# sch.net
KiCad netlist of a schematic drawn in Altium Designer
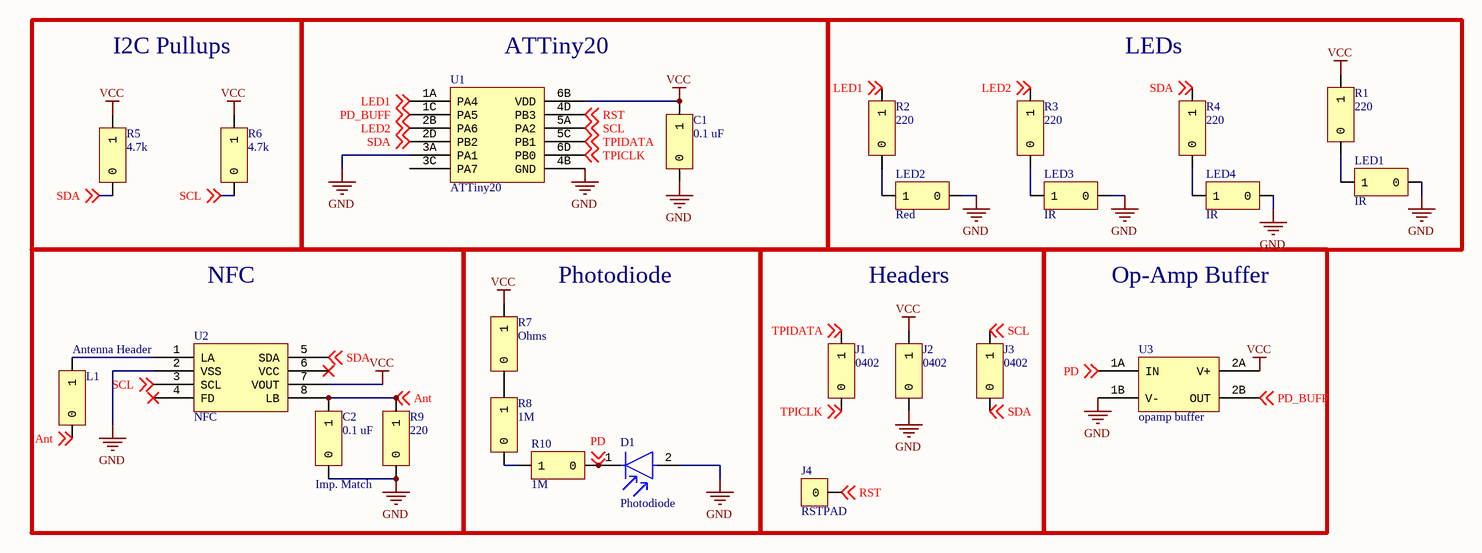
[diagram p0: sch.SchDoc]

(export (version "E")
  (design (tool "Eeschema 10.0.6"))
  (components
    (comp (ref "C1")
      (value "0.1 uF")
      (footprint "01005")
      (description "01005 Component")
      (fields (field (name "MPN") "CL02A104KQ2NNNC"))
      (libsource (lib "schlib") (part "01005"))
    )
    (comp (ref "C2")
      (value "0.1 uF")
      (footprint "01005")
      (description "01005 Component")
      (fields (field (name "MPN") "CL02A104KQ2NNNC"))
      (libsource (lib "schlib") (part "01005"))
    )
    (comp (ref "D1")
      (value "Photodiode")
      (footprint "FP-6_541-5064_01-4-MFG")
      (description "0805 PHOTODIODE\r\ntemd7000x01")
      (fields
        (field (name "MANUFACTURER") "Vishay")
        (field (name "OCTOPART") "https://octopart.com/temd6200fx01-vishay-19158932")
      )
      (libsource (lib "Altium Content Vault") (part "9b7c99953c265a88c20b8f1023d9605"))
    )
    (comp (ref "J1")
      (value "0402")
      (footprint "0402")
      (description "0402 Component")
      (libsource (lib "schlib") (part "0402"))
    )
    (comp (ref "J2")
      (value "0402")
      (footprint "0402")
      (description "0402 Component")
      (libsource (lib "schlib") (part "0402"))
    )
    (comp (ref "J3")
      (value "0402")
      (footprint "0402")
      (description "0402 Component")
      (libsource (lib "schlib") (part "0402"))
    )
    (comp (ref "J4") (value "RSTPAD") (footprint "RSTPAD") (libsource (lib "schlib") (part "RSTPAD")))
    (comp (ref "L1")
      (value "Antenna Header")
      (footprint "0402")
      (description "0402 Component")
      (libsource (lib "schlib") (part "0402"))
    )
    (comp (ref "LED1")
      (value "IR")
      (footprint "0402")
      (description "0402 Component\r\nSFH 4043")
      (fields (field (name "MPN") "SFH 4043"))
      (libsource (lib "") (part "0402_1"))
    )
    (comp (ref "LED2")
      (value "Red")
      (footprint "0201")
      (description "0201 Component\r\nXZMDR155W")
      (fields (field (name "MPN") "XZMDR155W"))
      (libsource (lib "schlib") (part "0201"))
    )
    (comp (ref "LED3")
      (value "IR")
      (footprint "0402")
      (description "0402 Component\r\nSFH 4043")
      (fields (field (name "MPN") "SFH 4043"))
      (libsource (lib "") (part "0402_1"))
    )
    (comp (ref "LED4")
      (value "IR")
      (footprint "0402")
      (description "0402 Component\r\nSFH 4043")
      (fields (field (name "MPN") "SFH 4043"))
      (libsource (lib "") (part "0402_1"))
    )
    (comp (ref "R1")
      (value "220")
      (footprint "01005")
      (description "01005 Component\r\nCRCW0100220RFREL")
      (fields (field (name "MPN") "CRCW0100220RFREL"))
      (libsource (lib "schlib") (part "01005"))
    )
    (comp (ref "R2")
      (value "220")
      (footprint "01005")
      (description "01005 Component\r\nCRCW0100220RFREL")
      (fields (field (name "MPN") "CRCW0100220RFREL"))
      (libsource (lib "schlib") (part "01005"))
    )
    (comp (ref "R3")
      (value "220")
      (footprint "01005")
      (description "01005 Component\r\nCRCW0100220RFREL")
      (fields (field (name "MPN") "CRCW0100220RFREL"))
      (libsource (lib "schlib") (part "01005"))
    )
    (comp (ref "R4")
      (value "220")
      (footprint "01005")
      (description "01005 Component\r\nCRCW0100220RFREL")
      (fields (field (name "MPN") "CRCW0100220RFREL"))
      (libsource (lib "schlib") (part "01005"))
    )
    (comp (ref "R5")
      (value "4.7k")
      (footprint "01005")
      (description "01005 Component")
      (fields (field (name "MPN") "CL02A104KQ2NNNC"))
      (libsource (lib "schlib") (part "01005"))
    )
    (comp (ref "R6")
      (value "4.7k")
      (footprint "01005")
      (description "01005 Component")
      (fields (field (name "MPN") "CL02A104KQ2NNNC"))
      (libsource (lib "schlib") (part "01005"))
    )
    (comp (ref "R7")
      (value "Ohms")
      (footprint "01005")
      (description "01005 Component\r\nCRCW01001M00FREL\r\n<Placeholder if more gain is necessary>")
      (fields (field (name "MPN") "CRCW01001M00FREL"))
      (libsource (lib "schlib") (part "01005"))
    )
    (comp (ref "R8")
      (value "1M")
      (footprint "01005")
      (description "01005 Component\r\nCRCW01001M00FREL")
      (fields (field (name "MPN") "CRCW01001M00FREL"))
      (libsource (lib "schlib") (part "01005"))
    )
    (comp (ref "R9")
      (value "220")
      (footprint "01005")
      (description "01005 Component\r\nCRCW0100220RFREL")
      (fields (field (name "MPN") "CRCW0100220RFREL"))
      (libsource (lib "schlib") (part "01005"))
    )
    (comp (ref "R10")
      (value "1M")
      (footprint "01005")
      (description "01005 Component\r\nCRCW01001M00FREL")
      (fields (field (name "MPN") "CRCW01001M00FREL"))
      (libsource (lib "") (part "01005_1"))
    )
    (comp (ref "U1")
      (value "ATTiny20")
      (footprint "Large_attiny")
      (libsource (lib "schlib") (part "ATTiny20"))
    )
    (comp (ref "U2") (value "NFC") (footprint "NFC") (libsource (lib "schlib") (part "NFC")))
    (comp (ref "U3") (value "opamp buffer") (footprint "opamp") (libsource (lib "schlib") (part "Op-amp")))
  )
  (nets
    (net (code "1") (name "Ant") (class "Default")
      (node (ref "C2") (pin "1") (pinfunction "1_1") (pintype "passive"))
      (node (ref "L1") (pin "0") (pinfunction "0_0") (pintype "passive"))
      (node (ref "R9") (pin "1") (pinfunction "1_1") (pintype "passive"))
      (node (ref "U2") (pin "8") (pinfunction "LB_8") (pintype "passive"))
    )
    (net (code "2") (name "GND") (class "Default")
      (node (ref "C1") (pin "0") (pinfunction "0_0") (pintype "passive"))
      (node (ref "C2") (pin "0") (pinfunction "0_0") (pintype "passive"))
      (node (ref "D1") (pin "2") (pinfunction "A_2") (pintype "passive"))
      (node (ref "J2") (pin "0") (pinfunction "0_0") (pintype "passive"))
      (node (ref "LED1") (pin "0") (pinfunction "0_0") (pintype "passive"))
      (node (ref "LED2") (pin "0") (pinfunction "0_0") (pintype "passive"))
      (node (ref "LED3") (pin "0") (pinfunction "0_0") (pintype "passive"))
      (node (ref "LED4") (pin "0") (pinfunction "0_0") (pintype "passive"))
      (node (ref "R9") (pin "0") (pinfunction "0_0") (pintype "passive"))
      (node (ref "U1") (pin "3A") (pinfunction "PA1_3A") (pintype "passive"))
      (node (ref "U1") (pin "4B") (pinfunction "GND_4B") (pintype "passive"))
      (node (ref "U2") (pin "2") (pinfunction "VSS_2") (pintype "passive"))
      (node (ref "U3") (pin "1B") (pinfunction "V-_1B") (pintype "passive"))
    )
    (net (code "3") (name "LED1") (class "Default")
      (node (ref "R2") (pin "1") (pinfunction "1_1") (pintype "passive"))
      (node (ref "U1") (pin "1A") (pinfunction "PA4_1A") (pintype "passive"))
    )
    (net (code "4") (name "LED2") (class "Default")
      (node (ref "R3") (pin "1") (pinfunction "1_1") (pintype "passive"))
      (node (ref "U1") (pin "2B") (pinfunction "PA6_2B") (pintype "passive"))
    )
    (net (code "5") (name "Net-(LED1-Pad1)") (class "Default")
      (node (ref "LED1") (pin "1") (pinfunction "1_1") (pintype "passive"))
      (node (ref "R1") (pin "0") (pinfunction "0_0") (pintype "passive"))
    )
    (net (code "6") (name "Net-(LED2-Pad1)") (class "Default")
      (node (ref "LED2") (pin "1") (pinfunction "1_1") (pintype "passive"))
      (node (ref "R2") (pin "0") (pinfunction "0_0") (pintype "passive"))
    )
    (net (code "7") (name "Net-(LED3-Pad1)") (class "Default")
      (node (ref "LED3") (pin "1") (pinfunction "1_1") (pintype "passive"))
      (node (ref "R3") (pin "0") (pinfunction "0_0") (pintype "passive"))
    )
    (net (code "8") (name "Net-(LED4-Pad1)") (class "Default")
      (node (ref "LED4") (pin "1") (pinfunction "1_1") (pintype "passive"))
      (node (ref "R4") (pin "0") (pinfunction "0_0") (pintype "passive"))
    )
    (net (code "9") (name "Net-(R7-Pad0)") (class "Default")
      (node (ref "R7") (pin "0") (pinfunction "0_0") (pintype "passive"))
      (node (ref "R8") (pin "1") (pinfunction "1_1") (pintype "passive"))
    )
    (net (code "10") (name "Net-(R10-Pad1)") (class "Default")
      (node (ref "R10") (pin "1") (pinfunction "1_1") (pintype "passive"))
      (node (ref "R8") (pin "0") (pinfunction "0_0") (pintype "passive"))
    )
    (net (code "11") (name "Net-(U2-LA)") (class "Default")
      (node (ref "L1") (pin "1") (pinfunction "1_1") (pintype "passive"))
      (node (ref "U2") (pin "1") (pinfunction "LA_1") (pintype "passive"))
    )
    (net (code "12") (name "PD") (class "Default")
      (node (ref "D1") (pin "1") (pinfunction "C_1") (pintype "passive"))
      (node (ref "R10") (pin "0") (pinfunction "0_0") (pintype "passive"))
      (node (ref "U3") (pin "1A") (pinfunction "IN_1A") (pintype "passive"))
    )
    (net (code "13") (name "PD_BUFF") (class "Default")
      (node (ref "U1") (pin "1C") (pinfunction "PA5_1C") (pintype "passive"))
      (node (ref "U3") (pin "2B") (pinfunction "OUT_2B") (pintype "passive"))
    )
    (net (code "14") (name "RST") (class "Default")
      (node (ref "J4") (pin "0") (pinfunction "0_0") (pintype "passive"))
      (node (ref "U1") (pin "4D") (pinfunction "PB3_4D") (pintype "passive"))
    )
    (net (code "15") (name "SCL") (class "Default")
      (node (ref "J3") (pin "1") (pinfunction "1_1") (pintype "passive"))
      (node (ref "R6") (pin "0") (pinfunction "0_0") (pintype "passive"))
      (node (ref "U1") (pin "5A") (pinfunction "PA2_5A") (pintype "passive"))
      (node (ref "U2") (pin "3") (pinfunction "SCL_3") (pintype "passive"))
    )
    (net (code "16") (name "SDA") (class "Default")
      (node (ref "J3") (pin "0") (pinfunction "0_0") (pintype "passive"))
      (node (ref "R4") (pin "1") (pinfunction "1_1") (pintype "passive"))
      (node (ref "R5") (pin "0") (pinfunction "0_0") (pintype "passive"))
      (node (ref "U1") (pin "2D") (pinfunction "PB2_2D") (pintype "passive"))
      (node (ref "U2") (pin "5") (pinfunction "SDA_5") (pintype "passive"))
    )
    (net (code "17") (name "TPICLK") (class "Default")
      (node (ref "J1") (pin "0") (pinfunction "0_0") (pintype "passive"))
      (node (ref "U1") (pin "6D") (pinfunction "PB0_6D") (pintype "passive"))
    )
    (net (code "18") (name "TPIDATA") (class "Default")
      (node (ref "J1") (pin "1") (pinfunction "1_1") (pintype "passive"))
      (node (ref "U1") (pin "5C") (pinfunction "PB1_5C") (pintype "passive"))
    )
    (net (code "19") (name "VCC") (class "Default")
      (node (ref "C1") (pin "1") (pinfunction "1_1") (pintype "passive"))
      (node (ref "J2") (pin "1") (pinfunction "1_1") (pintype "passive"))
      (node (ref "R1") (pin "1") (pinfunction "1_1") (pintype "passive"))
      (node (ref "R5") (pin "1") (pinfunction "1_1") (pintype "passive"))
      (node (ref "R6") (pin "1") (pinfunction "1_1") (pintype "passive"))
      (node (ref "R7") (pin "1") (pinfunction "1_1") (pintype "passive"))
      (node (ref "U1") (pin "6B") (pinfunction "VDD_6B") (pintype "passive"))
      (node (ref "U2") (pin "7") (pinfunction "VOUT_7") (pintype "passive"))
      (node (ref "U3") (pin "2A") (pinfunction "V+_2A") (pintype "passive"))
    )
    (net (code "20") (name "unconnected-(U1-PA7-Pad3C)") (class "Default")
      (node (ref "U1") (pin "3C") (pinfunction "PA7_3C") (pintype "passive"))
    )
    (net (code "21") (name "unconnected-(U2-FD-Pad4)") (class "Default")
      (node (ref "U2") (pin "4") (pinfunction "FD_4") (pintype "passive+no_connect"))
    )
    (net (code "22") (name "unconnected-(U2-VCC-Pad6)") (class "Default")
      (node (ref "U2") (pin "6") (pinfunction "VCC_6") (pintype "passive+no_connect"))
    )
  )
)
